# navigatie_switches.net
KiCad netlist of a schematic drawn in Altium Designer
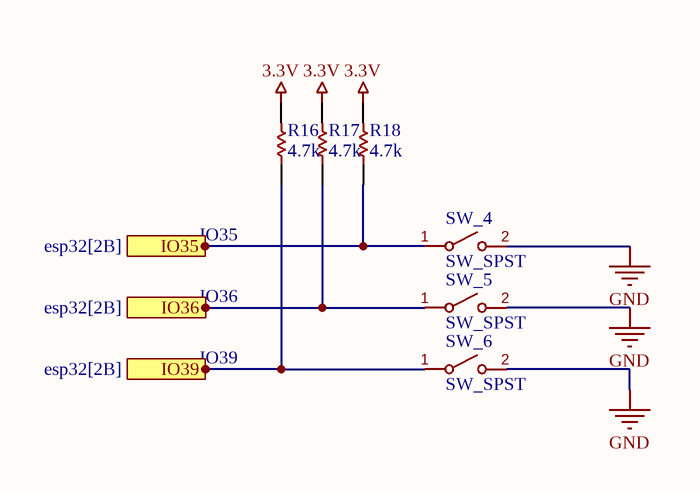
[diagram p0: navigatie_switches.SchDoc]

(export (version "E")
  (design (tool "Eeschema 10.0.6"))
  (components
    (comp (ref "R16")
      (value "4.7k")
      (footprint "RESC2013X70X40NL20T20")
      (description "Chip Resistor, 1 KOhm, +/- 1%, 125 mW, -55 to 155 degC, 0805 (2012 Metric), RoHS, Tape and Reel")
      (fields (field (name "TOLERANCE") "1%") (field (name "MANUFACTURER") "Yageo"))
      (libsource (lib "Thermal_Camera") (part "CMP-2100-03671-1"))
    )
    (comp (ref "R17")
      (value "4.7k")
      (footprint "RESC2013X70X40NL20T20")
      (description "Chip Resistor, 1 KOhm, +/- 1%, 125 mW, -55 to 155 degC, 0805 (2012 Metric), RoHS, Tape and Reel")
      (fields (field (name "TOLERANCE") "1%") (field (name "MANUFACTURER") "Yageo"))
      (libsource (lib "Thermal_Camera") (part "CMP-2100-03671-1"))
    )
    (comp (ref "R18")
      (value "4.7k")
      (footprint "RESC2013X70X40NL20T20")
      (description "Chip Resistor, 1 KOhm, +/- 1%, 125 mW, -55 to 155 degC, 0805 (2012 Metric), RoHS, Tape and Reel")
      (fields (field (name "TOLERANCE") "1%") (field (name "MANUFACTURER") "Yageo"))
      (libsource (lib "Thermal_Camera") (part "CMP-2100-03671-1"))
    )
    (comp (ref "SW_4")
      (value "SW_SPST")
      (footprint "SW_TS09-63-25-WT-160-SMT-TR")
      (libsource (lib "Thermal_Camera") (part "SW_SPST"))
    )
    (comp (ref "SW_5")
      (value "SW_SPST")
      (footprint "SW_TS09-63-25-WT-160-SMT-TR")
      (libsource (lib "Thermal_Camera") (part "SW_SPST"))
    )
    (comp (ref "SW_6")
      (value "SW_SPST")
      (footprint "SW_TS09-63-25-WT-160-SMT-TR")
      (libsource (lib "Thermal_Camera") (part "SW_SPST"))
    )
  )
  (nets
    (net (code "1") (name "/IO35") (class "Default")
      (node (ref "R18") (pin "1") (pinfunction "1_1") (pintype "passive"))
      (node (ref "SW_4") (pin "1") (pinfunction "A_1") (pintype "passive"))
    )
    (net (code "2") (name "/IO36") (class "Default")
      (node (ref "R17") (pin "1") (pinfunction "1_1") (pintype "passive"))
      (node (ref "SW_5") (pin "1") (pinfunction "A_1") (pintype "passive"))
    )
    (net (code "3") (name "/IO39") (class "Default")
      (node (ref "R16") (pin "1") (pinfunction "1_1") (pintype "passive"))
      (node (ref "SW_6") (pin "1") (pinfunction "A_1") (pintype "passive"))
    )
    (net (code "4") (name "3.3V") (class "Default")
      (node (ref "R16") (pin "2") (pinfunction "2_2") (pintype "passive"))
      (node (ref "R17") (pin "2") (pinfunction "2_2") (pintype "passive"))
      (node (ref "R18") (pin "2") (pinfunction "2_2") (pintype "passive"))
    )
    (net (code "5") (name "GND") (class "Default")
      (node (ref "SW_4") (pin "2") (pinfunction "B_2") (pintype "passive"))
      (node (ref "SW_5") (pin "2") (pinfunction "B_2") (pintype "passive"))
      (node (ref "SW_6") (pin "2") (pinfunction "B_2") (pintype "passive"))
    )
  )
)
